# RedBoard-Artemis-Nano.net
KiCad netlist of a schematic drawn in EAGLE
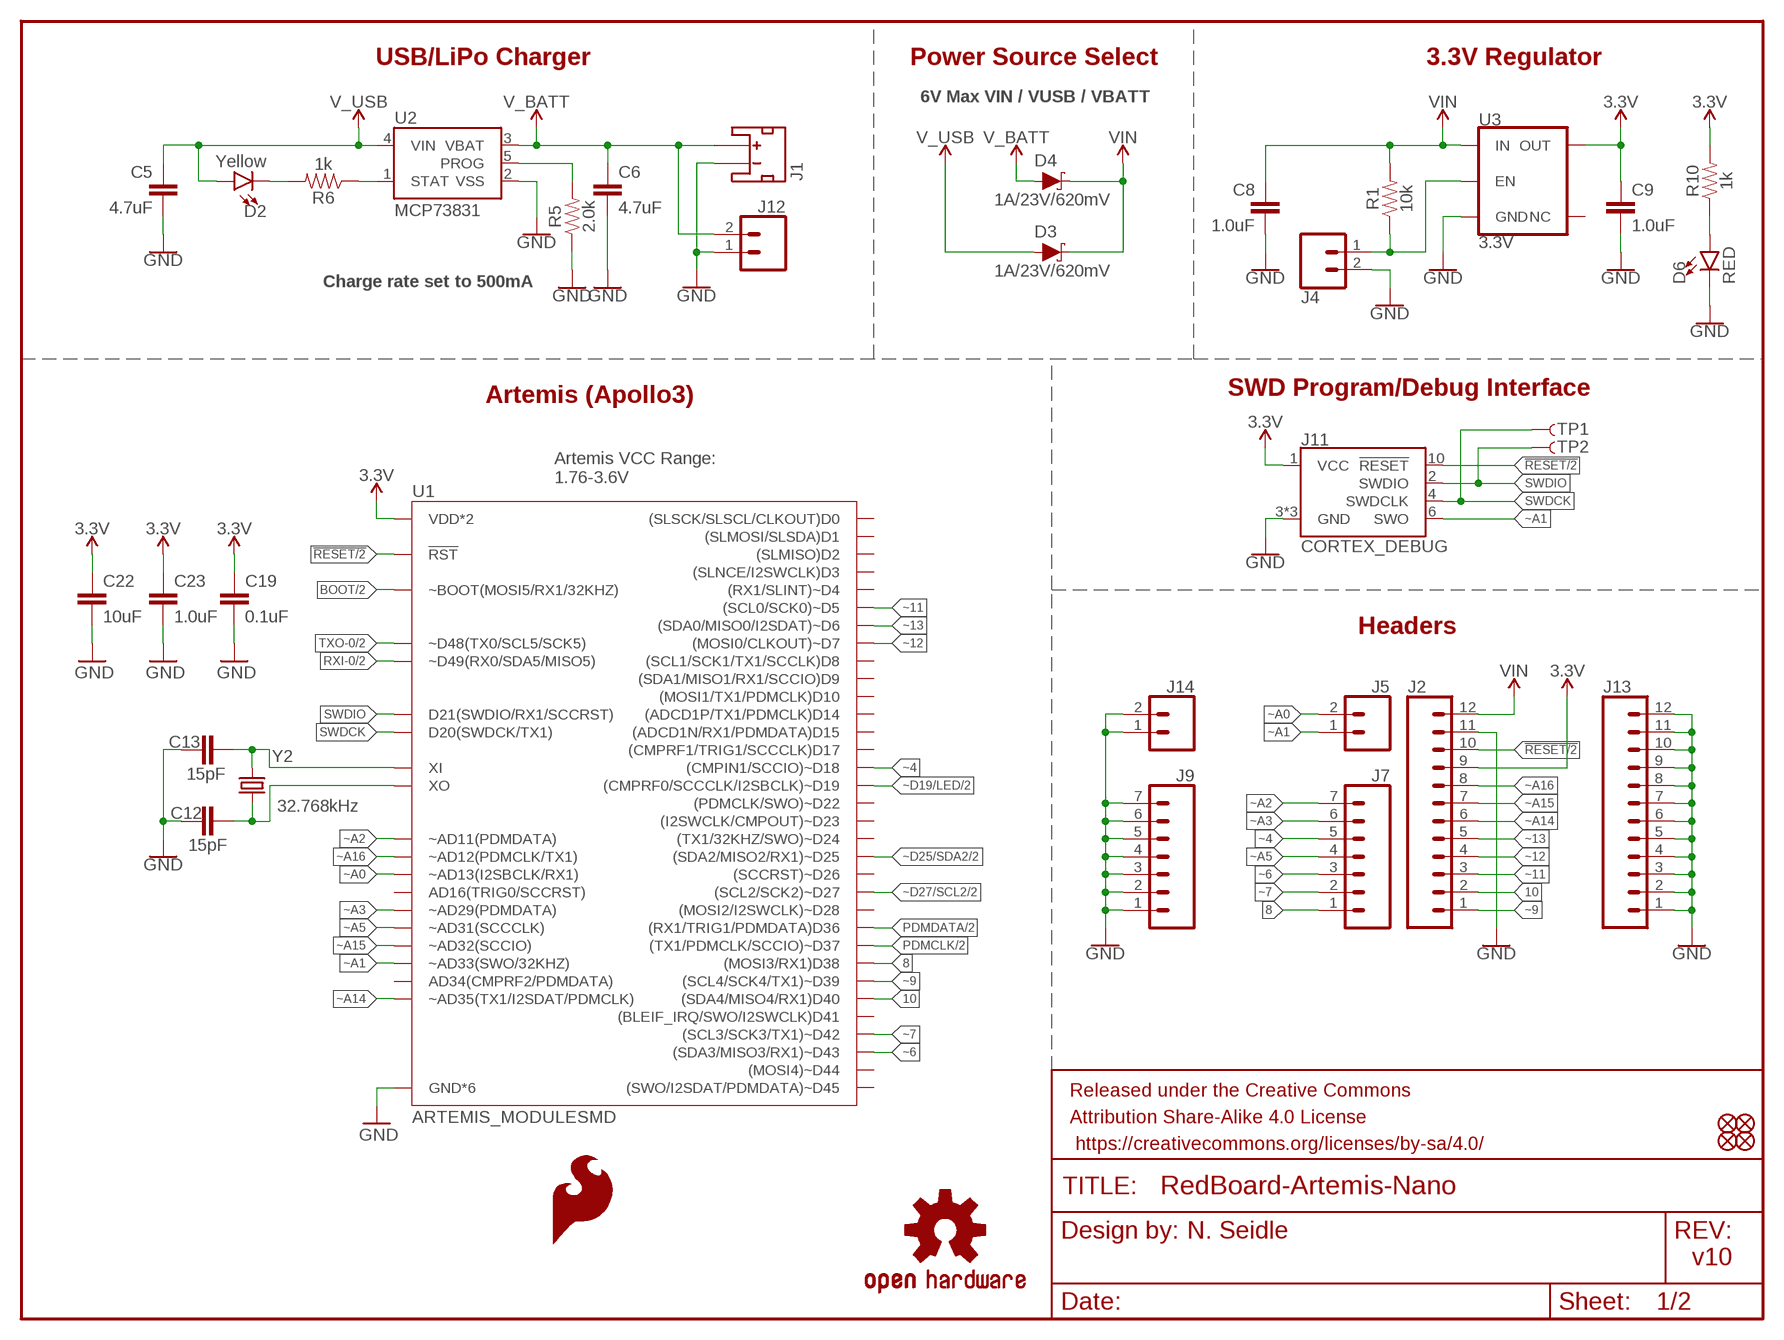
[diagram p0: schematic, sheet 1]
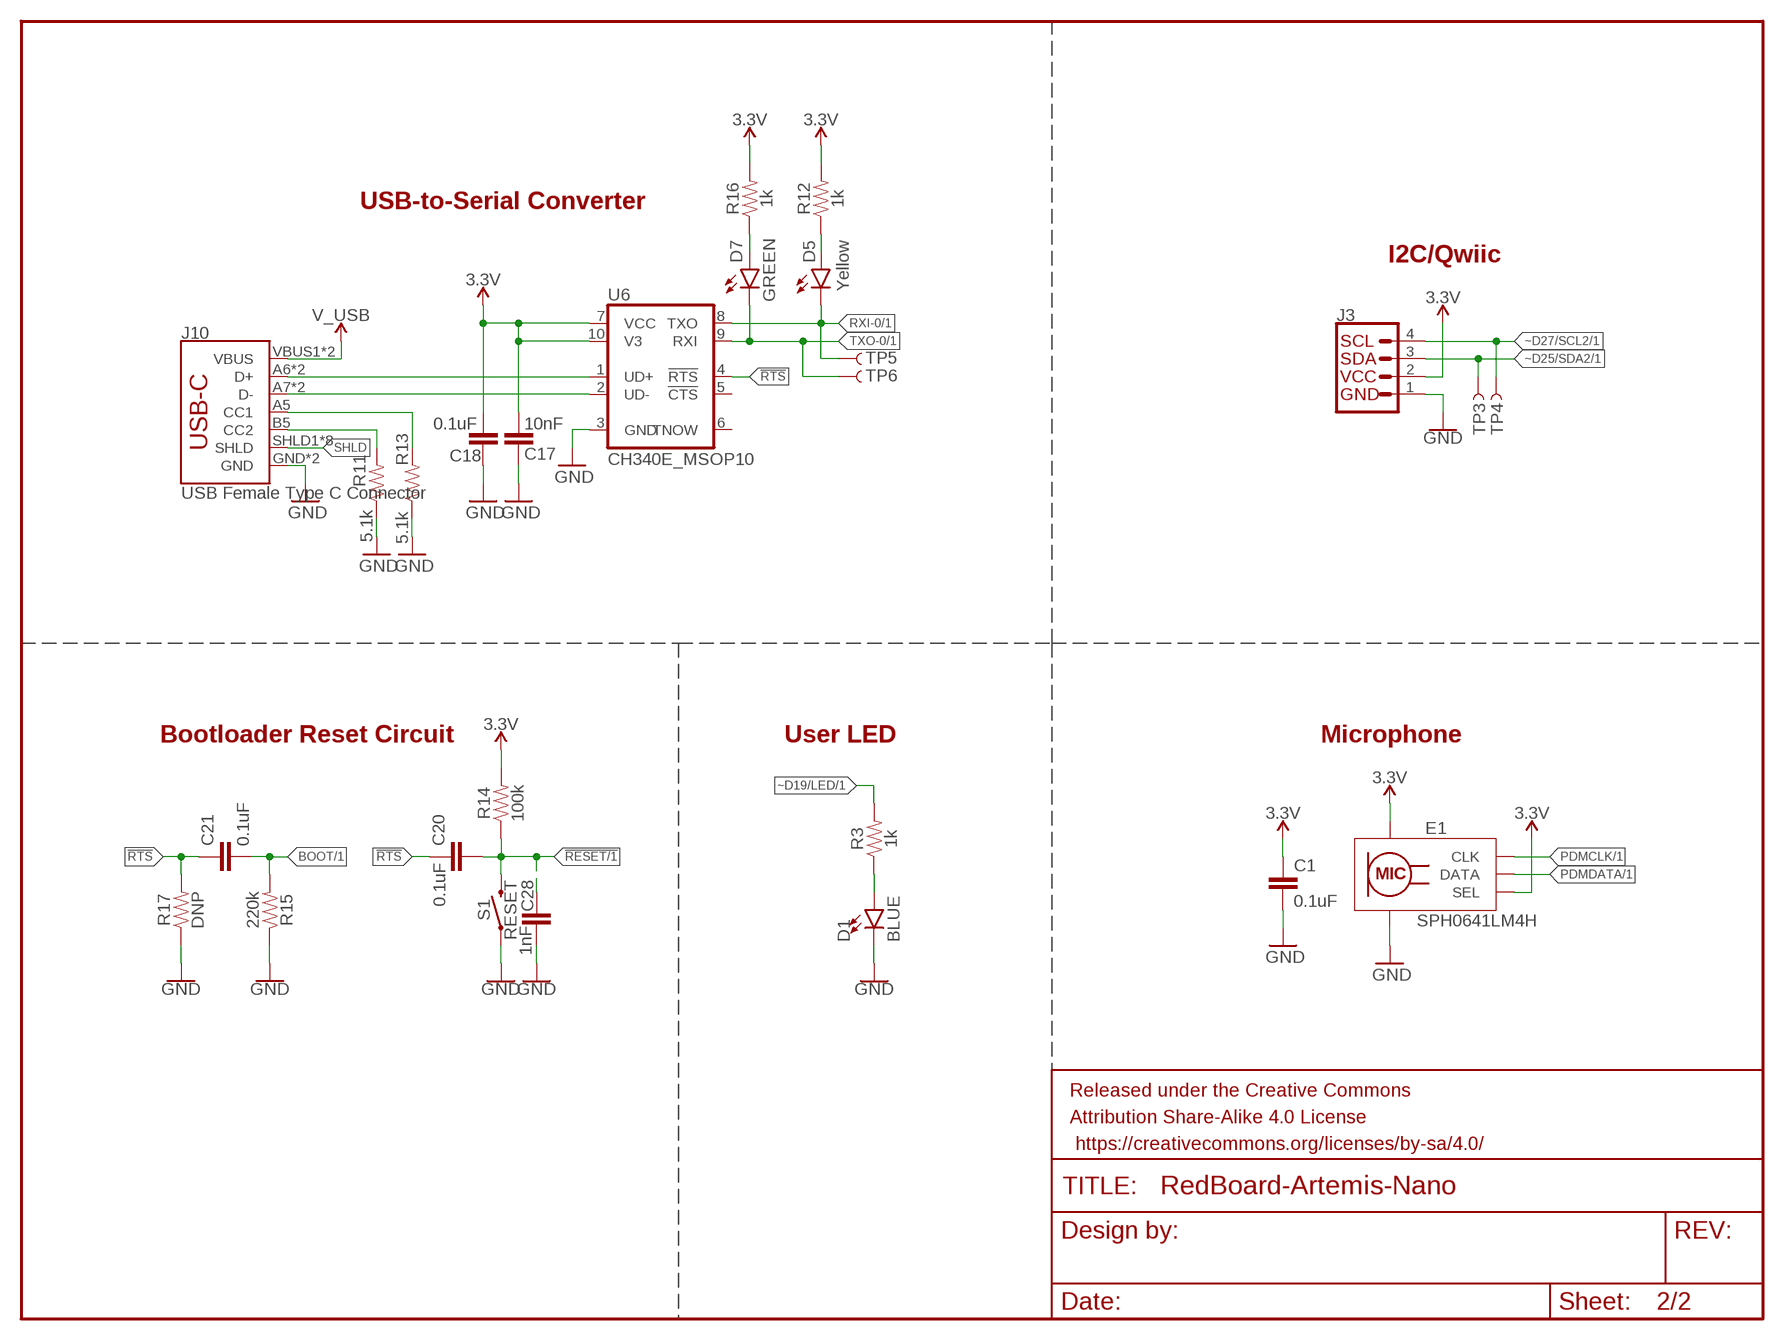
[diagram p1: schematic, sheet 2]

(export (version "E")
  (design (tool "Eeschema 10.0.6"))
  (components
    (comp (ref "C5")
      (value "4.7uF")
      (footprint "eagle-import:0603")
      (libsource (lib "eagle-import") (part "4.7UF-0603-6.3V-(10%)"))
    )
    (comp (ref "C6")
      (value "4.7uF")
      (footprint "eagle-import:0603")
      (libsource (lib "eagle-import") (part "4.7UF-0603-6.3V-(10%)"))
    )
    (comp (ref "C8")
      (value "1.0uF")
      (footprint "eagle-import:0402-TIGHT")
      (libsource (lib "eagle-import") (part "1.0UF-0402T-16V-10%"))
    )
    (comp (ref "C9")
      (value "1.0uF")
      (footprint "eagle-import:0402-TIGHT")
      (libsource (lib "eagle-import") (part "1.0UF-0402T-16V-10%"))
    )
    (comp (ref "C12")
      (value "15pF")
      (footprint "eagle-import:0603")
      (libsource (lib "eagle-import") (part "15PF-0603-50V-5%"))
    )
    (comp (ref "C13")
      (value "15pF")
      (footprint "eagle-import:0603")
      (libsource (lib "eagle-import") (part "15PF-0603-50V-5%"))
    )
    (comp (ref "C19")
      (value "0.1uF")
      (footprint "eagle-import:0402-TIGHT")
      (libsource (lib "eagle-import") (part "0.1UF-0402T-16V-10%"))
    )
    (comp (ref "C22")
      (value "10uF")
      (footprint "eagle-import:0603")
      (libsource (lib "eagle-import") (part "10UF-0603-6.3V-20%"))
    )
    (comp (ref "C23")
      (value "1.0uF")
      (footprint "eagle-import:0402-TIGHT")
      (libsource (lib "eagle-import") (part "1.0UF-0402T-16V-10%"))
    )
    (comp (ref "D2")
      (value "Yellow")
      (footprint "eagle-import:LED-0603")
      (libsource (lib "eagle-import") (part "LED-YELLOW0603"))
    )
    (comp (ref "D3")
      (value "1A/23V/620mV")
      (footprint "eagle-import:SOD-323")
      (libsource (lib "eagle-import") (part "DIODE-SCHOTTKY-BAT20J"))
    )
    (comp (ref "D4")
      (value "1A/23V/620mV")
      (footprint "eagle-import:SOD-323")
      (libsource (lib "eagle-import") (part "DIODE-SCHOTTKY-BAT20J"))
    )
    (comp (ref "D6")
      (value "RED")
      (footprint "eagle-import:LED-0603")
      (libsource (lib "eagle-import") (part "LED-RED0603"))
    )
    (comp (ref "FD1")
      (value "FIDUCIALUFIDUCIAL")
      (footprint "eagle-import:FIDUCIAL-MICRO")
      (libsource (lib "eagle-import") (part "FIDUCIALUFIDUCIAL"))
    )
    (comp (ref "FD2")
      (value "FIDUCIALUFIDUCIAL")
      (footprint "eagle-import:FIDUCIAL-MICRO")
      (libsource (lib "eagle-import") (part "FIDUCIALUFIDUCIAL"))
    )
    (comp (ref "FD3")
      (value "FIDUCIALUFIDUCIAL")
      (footprint "eagle-import:FIDUCIAL-MICRO")
      (libsource (lib "eagle-import") (part "FIDUCIALUFIDUCIAL"))
    )
    (comp (ref "FD4")
      (value "FIDUCIALUFIDUCIAL")
      (footprint "eagle-import:FIDUCIAL-MICRO")
      (libsource (lib "eagle-import") (part "FIDUCIALUFIDUCIAL"))
    )
    (comp (ref "FRAME1")
      (value "FRAME-LETTER")
      (footprint "eagle-import:CREATIVE_COMMONS")
      (libsource (lib "eagle-import") (part "FRAME-LETTER"))
    )
    (comp (ref "J1")
      (value "JST_2MM_MALE")
      (footprint "eagle-import:JST-2-SMD")
      (libsource (lib "eagle-import") (part "JST_2MM_MALE"))
    )
    (comp (ref "J2")
      (value "CONN_12NO_SILK")
      (footprint "eagle-import:1X12_NO_SILK")
      (libsource (lib "eagle-import") (part "CONN_12NO_SILK"))
    )
    (comp (ref "J4")
      (value "CONN_021X02_NO_SILK")
      (footprint "eagle-import:1X02_NO_SILK")
      (libsource (lib "eagle-import") (part "CONN_021X02_NO_SILK"))
    )
    (comp (ref "J5")
      (value "CONN_021X02_NO_SILK")
      (footprint "eagle-import:1X02_NO_SILK")
      (libsource (lib "eagle-import") (part "CONN_021X02_NO_SILK"))
    )
    (comp (ref "J7")
      (value "CONN_07NO_SILK")
      (footprint "eagle-import:1X07_NO_SILK")
      (libsource (lib "eagle-import") (part "CONN_07NO_SILK"))
    )
    (comp (ref "J9")
      (value "CONN_07NO_SILK")
      (footprint "eagle-import:1X07_NO_SILK")
      (libsource (lib "eagle-import") (part "CONN_07NO_SILK"))
    )
    (comp (ref "J11")
      (value "CORTEX_DEBUG")
      (footprint "eagle-import:2X5-PTH-1.27MM-NO_SILK")
      (libsource (lib "eagle-import") (part "CORTEX_JTAG_DEBUG_MINIMUM_PTH_NS"))
    )
    (comp (ref "J12")
      (value "CONN_021X02_NO_SILK")
      (footprint "eagle-import:1X02_NO_SILK")
      (libsource (lib "eagle-import") (part "CONN_021X02_NO_SILK"))
    )
    (comp (ref "J13")
      (value "CONN_12NO_SILK")
      (footprint "eagle-import:1X12_NO_SILK")
      (libsource (lib "eagle-import") (part "CONN_12NO_SILK"))
    )
    (comp (ref "J14")
      (value "CONN_021X02_NO_SILK")
      (footprint "eagle-import:1X02_NO_SILK")
      (libsource (lib "eagle-import") (part "CONN_021X02_NO_SILK"))
    )
    (comp (ref "LOGO1")
      (value "SFE_LOGO_FLAME.1_INCH")
      (footprint "eagle-import:SFE_LOGO_FLAME_.1")
      (libsource (lib "eagle-import") (part "SFE_LOGO_FLAME.1_INCH"))
    )
    (comp (ref "LOGO2")
      (value "OSHW-LOGONO_SILK")
      (footprint "eagle-import:DUMMY")
      (libsource (lib "eagle-import") (part "OSHW-LOGONO_SILK"))
    )
    (comp (ref "LOGO4")
      (value "SFE_LOGO_FLAME.1_INCH")
      (footprint "eagle-import:SFE_LOGO_FLAME_.1")
      (libsource (lib "eagle-import") (part "SFE_LOGO_FLAME.1_INCH"))
    )
    (comp (ref "R1")
      (value "10k")
      (footprint "eagle-import:0603")
      (libsource (lib "eagle-import") (part "10KOHM-0603-1/10W-1%"))
    )
    (comp (ref "R5")
      (value "2.0k")
      (footprint "eagle-import:0603")
      (libsource (lib "eagle-import") (part "2.0KOHM-0603-1/10W-5%"))
    )
    (comp (ref "R6")
      (value "1k")
      (footprint "eagle-import:0603")
      (libsource (lib "eagle-import") (part "1KOHM-0603-1/10W-1%"))
    )
    (comp (ref "R10")
      (value "1k")
      (footprint "eagle-import:0603")
      (libsource (lib "eagle-import") (part "1KOHM-0603-1/10W-1%"))
    )
    (comp (ref "TP1")
      (value "TEST-POINT3X5")
      (footprint "eagle-import:PAD.03X.05")
      (libsource (lib "eagle-import") (part "TEST-POINT3X5"))
    )
    (comp (ref "TP2")
      (value "TEST-POINT3X5")
      (footprint "eagle-import:PAD.03X.05")
      (libsource (lib "eagle-import") (part "TEST-POINT3X5"))
    )
    (comp (ref "U1")
      (value "ARTEMIS_MODULESMD")
      (footprint "eagle-import:ARTEMIS_FP")
      (libsource (lib "eagle-import") (part "ARTEMIS_MODULESMD"))
    )
    (comp (ref "U2")
      (value "MCP73831")
      (footprint "eagle-import:SOT23-5")
      (libsource (lib "eagle-import") (part "MCP73831"))
    )
    (comp (ref "U3")
      (value "3.3V")
      (footprint "eagle-import:SOT23-5")
      (libsource (lib "eagle-import") (part "V_REG_AP2112K-3.3V"))
    )
    (comp (ref "Y2")
      (value "32.768kHz")
      (footprint "eagle-import:CRYSTAL-SMD-3.2X1.5MM")
      (libsource (lib "eagle-import") (part "CRYSTAL-32.768KHZSMD-3.2X1.5"))
    )
    (comp (ref "C1")
      (value "0.1uF")
      (footprint "eagle-import:0402-TIGHT")
      (libsource (lib "eagle-import") (part "0.1UF-0402T-16V-10%"))
    )
    (comp (ref "C17")
      (value "10nF")
      (footprint "eagle-import:0603")
      (libsource (lib "eagle-import") (part "10NF-0603-50V-10%"))
    )
    (comp (ref "C18")
      (value "0.1uF")
      (footprint "eagle-import:0603")
      (libsource (lib "eagle-import") (part "0.1UF-0603-25V-(+80/-20%)"))
    )
    (comp (ref "C20")
      (value "0.1uF")
      (footprint "eagle-import:0603")
      (libsource (lib "eagle-import") (part "0.1UF-0603-25V-5%"))
    )
    (comp (ref "C21")
      (value "0.1uF")
      (footprint "eagle-import:0603")
      (libsource (lib "eagle-import") (part "0.1UF-0603-25V-5%"))
    )
    (comp (ref "C28")
      (value "1nF")
      (footprint "eagle-import:0603")
      (libsource (lib "eagle-import") (part "1.0NF/1000PF-0603-50V-10%"))
    )
    (comp (ref "D1")
      (value "BLUE")
      (footprint "eagle-import:LED-0603")
      (libsource (lib "eagle-import") (part "LED-BLUE0603"))
    )
    (comp (ref "D5")
      (value "Yellow")
      (footprint "eagle-import:LED-0603")
      (libsource (lib "eagle-import") (part "LED-YELLOW0603"))
    )
    (comp (ref "D7")
      (value "GREEN")
      (footprint "eagle-import:LED-0603")
      (libsource (lib "eagle-import") (part "LED-GREEN0603"))
    )
    (comp (ref "E1")
      (value "SPH0641LM4H")
      (footprint "eagle-import:SPH0641LM4H-1_MICROPHONE")
      (libsource (lib "eagle-import") (part "SPH0641LM4H-1_MICROPHONE"))
    )
    (comp (ref "FRAME2")
      (value "FRAME-LETTERNO_PACKAGE")
      (footprint "eagle-import:DUMMY")
      (fields (field (name "DESIGNER") "Nobody"))
      (libsource (lib "eagle-import") (part "FRAME-LETTERNO_PACKAGE"))
    )
    (comp (ref "J3")
      (value "QWIIC_CONNECTORJS-1MM")
      (footprint "eagle-import:JST04_1MM_RA")
      (libsource (lib "eagle-import") (part "QWIIC_CONNECTORJS-1MM"))
    )
    (comp (ref "J10")
      (value "USB Female Type C Connector")
      (footprint "eagle-import:USB-C-16P-4LAYER-ISOLATED")
      (libsource (lib "eagle-import") (part "USB_C4-LAYER-ISOLATED"))
    )
    (comp (ref "R3")
      (value "1k")
      (footprint "eagle-import:0603")
      (libsource (lib "eagle-import") (part "1KOHM-0603-1/10W-1%"))
    )
    (comp (ref "R11")
      (value "5.1k")
      (footprint "eagle-import:0603")
      (libsource (lib "eagle-import") (part "5.1KOHM5.1KOHM-0603-1/10W-1%"))
    )
    (comp (ref "R12")
      (value "1k")
      (footprint "eagle-import:0603")
      (libsource (lib "eagle-import") (part "1KOHM-0603-1/10W-1%"))
    )
    (comp (ref "R13")
      (value "5.1k")
      (footprint "eagle-import:0603")
      (libsource (lib "eagle-import") (part "5.1KOHM5.1KOHM-0603-1/10W-1%"))
    )
    (comp (ref "R14")
      (value "100k")
      (footprint "eagle-import:0603")
      (libsource (lib "eagle-import") (part "100KOHM-0603-1/10W-1%"))
    )
    (comp (ref "R15")
      (value "220k")
      (footprint "eagle-import:0603")
      (libsource (lib "eagle-import") (part "220KOHM-0603-1/10W-1%"))
    )
    (comp (ref "R16")
      (value "1k")
      (footprint "eagle-import:0603")
      (libsource (lib "eagle-import") (part "1KOHM-0603-1/10W-1%"))
    )
    (comp (ref "R17")
      (value "DNP")
      (footprint "eagle-import:0603")
      (libsource (lib "eagle-import") (part "RESISTOR0603"))
    )
    (comp (ref "S1")
      (value "RESET")
      (footprint "eagle-import:TACTILE_SWITCH_SMD_4.6X2.8MM")
      (libsource (lib "eagle-import") (part "MOMENTARY-SWITCH-SPST-SMD-4.6X2.8MM"))
    )
    (comp (ref "TP3")
      (value "TEST-POINT3X5")
      (footprint "eagle-import:PAD.03X.05")
      (libsource (lib "eagle-import") (part "TEST-POINT3X5"))
    )
    (comp (ref "TP4")
      (value "TEST-POINT3X5")
      (footprint "eagle-import:PAD.03X.05")
      (libsource (lib "eagle-import") (part "TEST-POINT3X5"))
    )
    (comp (ref "TP5")
      (value "TEST-POINT3X5")
      (footprint "eagle-import:PAD.03X.05")
      (libsource (lib "eagle-import") (part "TEST-POINT3X5"))
    )
    (comp (ref "TP6")
      (value "TEST-POINT3X5")
      (footprint "eagle-import:PAD.03X.05")
      (libsource (lib "eagle-import") (part "TEST-POINT3X5"))
    )
    (comp (ref "U6")
      (value "CH340E_MSOP10")
      (footprint "eagle-import:MSOP10")
      (libsource (lib "eagle-import") (part "CH340E_MSOP10"))
    )
  )
  (nets
    (net (code "1") (name "3.3V") (class "Default")
      (node (ref "C1") (pin "1") (pinfunction "1_1") (pintype "passive"))
      (node (ref "C17") (pin "1") (pinfunction "1_1") (pintype "passive"))
      (node (ref "C18") (pin "1") (pinfunction "1_1") (pintype "passive"))
      (node (ref "C19") (pin "2") (pinfunction "2_2") (pintype "passive"))
      (node (ref "C22") (pin "1") (pinfunction "1_1") (pintype "passive"))
      (node (ref "C23") (pin "1") (pinfunction "1_1") (pintype "passive"))
      (node (ref "C9") (pin "1") (pinfunction "1_1") (pintype "passive"))
      (node (ref "E1") (pin "2") (pinfunction "SEL_2") (pintype "input"))
      (node (ref "E1") (pin "5") (pinfunction "VDD_5") (pintype "power_in"))
      (node (ref "J11") (pin "1") (pinfunction "VCC_1") (pintype "bidirectional"))
      (node (ref "J2") (pin "9") (pinfunction "9_9") (pintype "passive"))
      (node (ref "J3") (pin "2") (pinfunction "2_2") (pintype "power_in"))
      (node (ref "R10") (pin "2") (pinfunction "2_2") (pintype "passive"))
      (node (ref "R12") (pin "2") (pinfunction "2_2") (pintype "passive"))
      (node (ref "R14") (pin "2") (pinfunction "2_2") (pintype "passive"))
      (node (ref "R16") (pin "2") (pinfunction "2_2") (pintype "passive"))
      (node (ref "U1") (pin "VDD@36") (pinfunction "VDD*2_VDD@36") (pintype "bidirectional"))
      (node (ref "U1") (pin "VDD@37") (pinfunction "VDD*2_VDD@37") (pintype "bidirectional"))
      (node (ref "U3") (pin "5") (pinfunction "OUT_5") (pintype "passive"))
      (node (ref "U6") (pin "10") (pinfunction "V3_10") (pintype "bidirectional"))
      (node (ref "U6") (pin "7") (pinfunction "VCC_7") (pintype "bidirectional"))
    )
    (net (code "2") (name "8") (class "Default")
      (node (ref "J7") (pin "1") (pinfunction "1_1") (pintype "passive"))
      (node (ref "U1") (pin "D38") (pinfunction "(MOSI3/RX1)D38_D38") (pintype "bidirectional"))
    )
    (net (code "3") (name "10") (class "Default")
      (node (ref "J2") (pin "2") (pinfunction "2_2") (pintype "passive"))
      (node (ref "U1") (pin "D40") (pinfunction "(SDA4/MISO4/RX1)D40_D40") (pintype "bidirectional"))
    )
    (net (code "4") (name "BOOT") (class "Default")
      (node (ref "C21") (pin "2") (pinfunction "2_2") (pintype "passive"))
      (node (ref "R15") (pin "2") (pinfunction "2_2") (pintype "passive"))
      (node (ref "U1") (pin "BOOT") (pinfunction "~{BOOT(MOSI5/RX1/32KHZ})_BOOT") (pintype "bidirectional"))
    )
    (net (code "5") (name "GND") (class "Default")
      (node (ref "C1") (pin "2") (pinfunction "2_2") (pintype "passive"))
      (node (ref "C12") (pin "1") (pinfunction "1_1") (pintype "passive"))
      (node (ref "C13") (pin "1") (pinfunction "1_1") (pintype "passive"))
      (node (ref "C17") (pin "2") (pinfunction "2_2") (pintype "passive"))
      (node (ref "C18") (pin "2") (pinfunction "2_2") (pintype "passive"))
      (node (ref "C19") (pin "1") (pinfunction "1_1") (pintype "passive"))
      (node (ref "C22") (pin "2") (pinfunction "2_2") (pintype "passive"))
      (node (ref "C23") (pin "2") (pinfunction "2_2") (pintype "passive"))
      (node (ref "C28") (pin "2") (pinfunction "2_2") (pintype "passive"))
      (node (ref "C5") (pin "2") (pinfunction "2_2") (pintype "passive"))
      (node (ref "C6") (pin "2") (pinfunction "2_2") (pintype "passive"))
      (node (ref "C8") (pin "2") (pinfunction "2_2") (pintype "passive"))
      (node (ref "C9") (pin "2") (pinfunction "2_2") (pintype "passive"))
      (node (ref "D1") (pin "C") (pinfunction "C_C") (pintype "passive"))
      (node (ref "D6") (pin "C") (pinfunction "C_C") (pintype "passive"))
      (node (ref "E1") (pin "3") (pinfunction "GND_3") (pintype "power_in"))
      (node (ref "E1") (pin "6") (pinfunction "GND_6") (pintype "power_in"))
      (node (ref "E1") (pin "7") (pinfunction "GND_7") (pintype "power_in"))
      (node (ref "E1") (pin "8") (pinfunction "GND_8") (pintype "power_in"))
      (node (ref "J1") (pin "1") (pinfunction "-_1") (pintype "bidirectional"))
      (node (ref "J10") (pin "GND") (pinfunction "GND_GND") (pintype "bidirectional"))
      (node (ref "J10") (pin "GND2") (pinfunction "GND_GND2") (pintype "bidirectional"))
      (node (ref "J11") (pin "3") (pinfunction "GND_3") (pintype "bidirectional"))
      (node (ref "J11") (pin "5") (pinfunction "GND_5") (pintype "bidirectional"))
      (node (ref "J11") (pin "9") (pinfunction "GND_9") (pintype "bidirectional"))
      (node (ref "J12") (pin "1") (pinfunction "1_1") (pintype "passive"))
      (node (ref "J13") (pin "1") (pinfunction "1_1") (pintype "passive"))
      (node (ref "J13") (pin "10") (pinfunction "10_10") (pintype "passive"))
      (node (ref "J13") (pin "11") (pinfunction "11_11") (pintype "passive"))
      (node (ref "J13") (pin "12") (pinfunction "12_12") (pintype "passive"))
      (node (ref "J13") (pin "2") (pinfunction "2_2") (pintype "passive"))
      (node (ref "J13") (pin "3") (pinfunction "3_3") (pintype "passive"))
      (node (ref "J13") (pin "4") (pinfunction "4_4") (pintype "passive"))
      (node (ref "J13") (pin "5") (pinfunction "5_5") (pintype "passive"))
      (node (ref "J13") (pin "6") (pinfunction "6_6") (pintype "passive"))
      (node (ref "J13") (pin "7") (pinfunction "7_7") (pintype "passive"))
      (node (ref "J13") (pin "8") (pinfunction "8_8") (pintype "passive"))
      (node (ref "J13") (pin "9") (pinfunction "9_9") (pintype "passive"))
      (node (ref "J14") (pin "1") (pinfunction "1_1") (pintype "passive"))
      (node (ref "J14") (pin "2") (pinfunction "2_2") (pintype "passive"))
      (node (ref "J2") (pin "11") (pinfunction "11_11") (pintype "passive"))
      (node (ref "J3") (pin "1") (pinfunction "1_1") (pintype "power_in"))
      (node (ref "J4") (pin "2") (pinfunction "2_2") (pintype "passive"))
      (node (ref "J9") (pin "1") (pinfunction "1_1") (pintype "passive"))
      (node (ref "J9") (pin "2") (pinfunction "2_2") (pintype "passive"))
      (node (ref "J9") (pin "3") (pinfunction "3_3") (pintype "passive"))
      (node (ref "J9") (pin "4") (pinfunction "4_4") (pintype "passive"))
      (node (ref "J9") (pin "5") (pinfunction "5_5") (pintype "passive"))
      (node (ref "J9") (pin "6") (pinfunction "6_6") (pintype "passive"))
      (node (ref "J9") (pin "7") (pinfunction "7_7") (pintype "passive"))
      (node (ref "R11") (pin "1") (pinfunction "1_1") (pintype "passive"))
      (node (ref "R13") (pin "1") (pinfunction "1_1") (pintype "passive"))
      (node (ref "R15") (pin "1") (pinfunction "1_1") (pintype "passive"))
      (node (ref "R17") (pin "1") (pinfunction "1_1") (pintype "passive"))
      (node (ref "R5") (pin "1") (pinfunction "1_1") (pintype "passive"))
      (node (ref "S1") (pin "1") (pinfunction "1_1") (pintype "passive"))
      (node (ref "S1") (pin "2") (pinfunction "1_2") (pintype "passive"))
      (node (ref "U1") (pin "GND@1") (pinfunction "GND*6_GND@1") (pintype "bidirectional"))
      (node (ref "U1") (pin "GND@22") (pinfunction "GND*6_GND@22") (pintype "bidirectional"))
      (node (ref "U1") (pin "GND@38") (pinfunction "GND*6_GND@38") (pintype "bidirectional"))
      (node (ref "U1") (pin "GND@39") (pinfunction "GND*6_GND@39") (pintype "bidirectional"))
      (node (ref "U1") (pin "GND@47") (pinfunction "GND*6_GND@47") (pintype "bidirectional"))
      (node (ref "U1") (pin "GND@59") (pinfunction "GND*6_GND@59") (pintype "bidirectional"))
      (node (ref "U2") (pin "2") (pinfunction "VSS_2") (pintype "power_in"))
      (node (ref "U3") (pin "2") (pinfunction "GND_2") (pintype "input"))
      (node (ref "U6") (pin "3") (pinfunction "GND_3") (pintype "bidirectional"))
    )
    (net (code "6") (name "Net-(D1-PadA)") (class "Default")
      (node (ref "D1") (pin "A") (pinfunction "A_A") (pintype "passive"))
      (node (ref "R3") (pin "1") (pinfunction "1_1") (pintype "passive"))
    )
    (net (code "7") (name "Net-(D2-PadC)") (class "Default")
      (node (ref "D2") (pin "C") (pinfunction "C_C") (pintype "passive"))
      (node (ref "R6") (pin "2") (pinfunction "2_2") (pintype "passive"))
    )
    (net (code "8") (name "Net-(D5-PadA)") (class "Default")
      (node (ref "D5") (pin "A") (pinfunction "A_A") (pintype "passive"))
      (node (ref "R12") (pin "1") (pinfunction "1_1") (pintype "passive"))
    )
    (net (code "9") (name "Net-(D6-PadA)") (class "Default")
      (node (ref "D6") (pin "A") (pinfunction "A_A") (pintype "passive"))
      (node (ref "R10") (pin "1") (pinfunction "1_1") (pintype "passive"))
    )
    (net (code "10") (name "Net-(D7-PadA)") (class "Default")
      (node (ref "D7") (pin "A") (pinfunction "A_A") (pintype "passive"))
      (node (ref "R16") (pin "1") (pinfunction "1_1") (pintype "passive"))
    )
    (net (code "11") (name "Net-(J10-CC1)") (class "Default")
      (node (ref "J10") (pin "A5") (pinfunction "CC1_A5") (pintype "bidirectional"))
      (node (ref "R13") (pin "2") (pinfunction "2_2") (pintype "passive"))
    )
    (net (code "12") (name "Net-(J10-CC2)") (class "Default")
      (node (ref "J10") (pin "B5") (pinfunction "CC2_B5") (pintype "bidirectional"))
      (node (ref "R11") (pin "2") (pinfunction "2_2") (pintype "passive"))
    )
    (net (code "13") (name "Net-(U2-PROG)") (class "Default")
      (node (ref "R5") (pin "2") (pinfunction "2_2") (pintype "passive"))
      (node (ref "U2") (pin "5") (pinfunction "PROG_5") (pintype "input"))
    )
    (net (code "14") (name "Net-(U2-STAT)") (class "Default")
      (node (ref "R6") (pin "1") (pinfunction "1_1") (pintype "passive"))
      (node (ref "U2") (pin "1") (pinfunction "STAT_1") (pintype "output"))
    )
    (net (code "15") (name "Net-(U3-EN)") (class "Default")
      (node (ref "J4") (pin "1") (pinfunction "1_1") (pintype "passive"))
      (node (ref "R1") (pin "1") (pinfunction "1_1") (pintype "passive"))
      (node (ref "U3") (pin "3") (pinfunction "EN_3") (pintype "input"))
    )
    (net (code "16") (name "Net-(U6-UD+)") (class "Default")
      (node (ref "J10") (pin "A6") (pinfunction "D+_A6") (pintype "bidirectional"))
      (node (ref "J10") (pin "B6") (pinfunction "D+_B6") (pintype "bidirectional"))
      (node (ref "U6") (pin "1") (pinfunction "UD+_1") (pintype "bidirectional"))
    )
    (net (code "17") (name "Net-(U6-UD-)") (class "Default")
      (node (ref "J10") (pin "A7") (pinfunction "D-_A7") (pintype "bidirectional"))
      (node (ref "J10") (pin "B7") (pinfunction "D-_B7") (pintype "bidirectional"))
      (node (ref "U6") (pin "2") (pinfunction "UD-_2") (pintype "bidirectional"))
    )
    (net (code "18") (name "Net-(Y2-1)") (class "Default")
      (node (ref "C13") (pin "2") (pinfunction "2_2") (pintype "passive"))
      (node (ref "U1") (pin "XI") (pinfunction "XI_XI") (pintype "bidirectional"))
      (node (ref "Y2") (pin "P$1") (pinfunction "1_P$1") (pintype "passive"))
    )
    (net (code "19") (name "Net-(Y2-2)") (class "Default")
      (node (ref "C12") (pin "2") (pinfunction "2_2") (pintype "passive"))
      (node (ref "U1") (pin "XO") (pinfunction "XO_XO") (pintype "bidirectional"))
      (node (ref "Y2") (pin "P$2") (pinfunction "2_P$2") (pintype "passive"))
    )
    (net (code "20") (name "PDMCLK") (class "Default")
      (node (ref "E1") (pin "4") (pinfunction "CLK_4") (pintype "input"))
      (node (ref "U1") (pin "~D37") (pinfunction "(TX1/PDMCLK/SCCIO)~{D37}_~D37") (pintype "bidirectional"))
    )
    (net (code "21") (name "PDMDATA") (class "Default")
      (node (ref "E1") (pin "1") (pinfunction "DATA_1") (pintype "output"))
      (node (ref "U1") (pin "D36") (pinfunction "(RX1/TRIG1/PDMDATA)D36_D36") (pintype "bidirectional"))
    )
    (net (code "22") (name "RXI-0") (class "Default")
      (node (ref "D5") (pin "C") (pinfunction "C_C") (pintype "passive"))
      (node (ref "TP5") (pin "P$1") (pinfunction "1_P$1") (pintype "bidirectional"))
      (node (ref "U1") (pin "RXI-0") (pinfunction "~{D49(RX0/SDA5/MISO5})_RXI-0") (pintype "bidirectional"))
      (node (ref "U6") (pin "8") (pinfunction "TXO_8") (pintype "bidirectional"))
    )
    (net (code "23") (name "SHLD") (class "Default")
      (node (ref "J10") (pin "SHLD1") (pinfunction "SHLD_SHLD1") (pintype "bidirectional"))
      (node (ref "J10") (pin "SHLD2") (pinfunction "SHLD_SHLD2") (pintype "bidirectional"))
      (node (ref "J10") (pin "SHLD3") (pinfunction "SHLD_SHLD3") (pintype "bidirectional"))
      (node (ref "J10") (pin "SHLD4") (pinfunction "SHLD_SHLD4") (pintype "bidirectional"))
      (node (ref "J10") (pin "SHLD5") (pinfunction "SHLD_SHLD5") (pintype "bidirectional"))
      (node (ref "J10") (pin "SHLD6") (pinfunction "SHLD_SHLD6") (pintype "bidirectional"))
      (node (ref "J10") (pin "SHLD7") (pinfunction "SHLD_SHLD7") (pintype "bidirectional"))
      (node (ref "J10") (pin "SHLD8") (pinfunction "SHLD_SHLD8") (pintype "bidirectional"))
    )
    (net (code "24") (name "SWDCK") (class "Default")
      (node (ref "J11") (pin "4") (pinfunction "SWDCLK_4") (pintype "bidirectional"))
      (node (ref "TP1") (pin "P$1") (pinfunction "1_P$1") (pintype "bidirectional"))
      (node (ref "U1") (pin "SWDCK") (pinfunction "D20(SWDCK/TX1)_SWDCK") (pintype "bidirectional"))
    )
    (net (code "25") (name "SWDIO") (class "Default")
      (node (ref "J11") (pin "2") (pinfunction "SWDIO_2") (pintype "bidirectional"))
      (node (ref "TP2") (pin "P$1") (pinfunction "1_P$1") (pintype "bidirectional"))
      (node (ref "U1") (pin "SWDIO") (pinfunction "D21(SWDIO/RX1/SCCRST)_SWDIO") (pintype "bidirectional"))
    )
    (net (code "26") (name "TXO-0") (class "Default")
      (node (ref "D7") (pin "C") (pinfunction "C_C") (pintype "passive"))
      (node (ref "TP6") (pin "P$1") (pinfunction "1_P$1") (pintype "bidirectional"))
      (node (ref "U1") (pin "TXO-0") (pinfunction "~{D48(TX0/SCL5/SCK5})_TXO-0") (pintype "bidirectional"))
      (node (ref "U6") (pin "9") (pinfunction "RXI_9") (pintype "bidirectional"))
    )
    (net (code "27") (name "VIN") (class "Default")
      (node (ref "C8") (pin "1") (pinfunction "1_1") (pintype "passive"))
      (node (ref "D3") (pin "C") (pinfunction "C_C") (pintype "passive"))
      (node (ref "D4") (pin "C") (pinfunction "C_C") (pintype "passive"))
      (node (ref "J2") (pin "12") (pinfunction "12_12") (pintype "passive"))
      (node (ref "R1") (pin "2") (pinfunction "2_2") (pintype "passive"))
      (node (ref "U3") (pin "1") (pinfunction "IN_1") (pintype "input"))
    )
    (net (code "28") (name "V_BATT") (class "Default")
      (node (ref "C6") (pin "1") (pinfunction "1_1") (pintype "passive"))
      (node (ref "D4") (pin "A") (pinfunction "A_A") (pintype "passive"))
      (node (ref "J1") (pin "2") (pinfunction "+_2") (pintype "bidirectional"))
      (node (ref "J12") (pin "2") (pinfunction "2_2") (pintype "passive"))
      (node (ref "U2") (pin "3") (pinfunction "VBAT_3") (pintype "power_in"))
    )
    (net (code "29") (name "V_USB") (class "Default")
      (node (ref "C5") (pin "1") (pinfunction "1_1") (pintype "passive"))
      (node (ref "D2") (pin "A") (pinfunction "A_A") (pintype "passive"))
      (node (ref "D3") (pin "A") (pinfunction "A_A") (pintype "passive"))
      (node (ref "J10") (pin "VBUS1") (pinfunction "VBUS_VBUS1") (pintype "bidirectional"))
      (node (ref "J10") (pin "VBUS2") (pinfunction "VBUS_VBUS2") (pintype "bidirectional"))
      (node (ref "U2") (pin "4") (pinfunction "VIN_4") (pintype "power_in"))
    )
    (net (code "30") (name "unconnected-(J1-PAD1-PadNC1)") (class "Default")
      (node (ref "J1") (pin "NC1") (pinfunction "PAD1_NC1") (pintype "bidirectional"))
    )
    (net (code "31") (name "unconnected-(J1-PAD2-PadNC2)") (class "Default")
      (node (ref "J1") (pin "NC2") (pinfunction "PAD2_NC2") (pintype "bidirectional"))
    )
    (net (code "32") (name "unconnected-(U1-(ADCD1N{slash}RX1{slash}PDMDATA)D15-PadD15)") (class "Default")
      (node (ref "U1") (pin "D15") (pinfunction "(ADCD1N/RX1/PDMDATA)D15_D15") (pintype "bidirectional"))
    )
    (net (code "33") (name "unconnected-(U1-(ADCD1P{slash}TX1{slash}PDMCLK)D14-PadD14)") (class "Default")
      (node (ref "U1") (pin "D14") (pinfunction "(ADCD1P/TX1/PDMCLK)D14_D14") (pintype "bidirectional"))
    )
    (net (code "34") (name "unconnected-(U1-(BLEIF_IRQ{slash}SWO{slash}I2SWCLK)D41-PadD41)") (class "Default")
      (node (ref "U1") (pin "D41") (pinfunction "(BLEIF_IRQ/SWO/I2SWCLK)D41_D41") (pintype "bidirectional"))
    )
    (net (code "35") (name "unconnected-(U1-(CMPRF1{slash}TRIG1{slash}SCCCLK)D17-PadD17)") (class "Default")
      (node (ref "U1") (pin "D17") (pinfunction "(CMPRF1/TRIG1/SCCCLK)D17_D17") (pintype "bidirectional"))
    )
    (net (code "36") (name "unconnected-(U1-(I2SWCLK{slash}CMPOUT)~{D23}-Pad~D23)") (class "Default")
      (node (ref "U1") (pin "~D23") (pinfunction "(I2SWCLK/CMPOUT)~{D23}_~D23") (pintype "bidirectional"))
    )
    (net (code "37") (name "unconnected-(U1-(MOSI1{slash}TX1{slash}PDMCLK)D10-PadD10)") (class "Default")
      (node (ref "U1") (pin "D10") (pinfunction "(MOSI1/TX1/PDMCLK)D10_D10") (pintype "bidirectional"))
    )
    (net (code "38") (name "unconnected-(U1-(MOSI2{slash}I2SWCLK)~{D28}-Pad~D28)") (class "Default")
      (node (ref "U1") (pin "~D28") (pinfunction "(MOSI2/I2SWCLK)~{D28}_~D28") (pintype "bidirectional"))
    )
    (net (code "39") (name "unconnected-(U1-(MOSI4)~{D44}-Pad~D44)") (class "Default")
      (node (ref "U1") (pin "~D44") (pinfunction "(MOSI4)~{D44}_~D44") (pintype "bidirectional"))
    )
    (net (code "40") (name "unconnected-(U1-(PDMCLK{slash}SWO)~{D22}-Pad~D22)") (class "Default")
      (node (ref "U1") (pin "~D22") (pinfunction "(PDMCLK/SWO)~{D22}_~D22") (pintype "bidirectional"))
    )
    (net (code "41") (name "unconnected-(U1-(RX1{slash}SLINT)~{D4}-Pad~D4)") (class "Default")
      (node (ref "U1") (pin "~D4") (pinfunction "(RX1/SLINT)~{D4}_~D4") (pintype "bidirectional"))
    )
    (net (code "42") (name "unconnected-(U1-(SCCRST)~{D26}-Pad~D26)") (class "Default")
      (node (ref "U1") (pin "~D26") (pinfunction "(SCCRST)~{D26}_~D26") (pintype "bidirectional"))
    )
    (net (code "43") (name "unconnected-(U1-(SCL1{slash}SCK1{slash}TX1{slash}SCCLK)D8-PadD8)") (class "Default")
      (node (ref "U1") (pin "D8") (pinfunction "(SCL1/SCK1/TX1/SCCLK)D8_D8") (pintype "bidirectional"))
    )
    (net (code "44") (name "unconnected-(U1-(SDA1{slash}MISO1{slash}RX1{slash}SCCIO)D9-PadD9)") (class "Default")
      (node (ref "U1") (pin "D9") (pinfunction "(SDA1/MISO1/RX1/SCCIO)D9_D9") (pintype "bidirectional"))
    )
    (net (code "45") (name "unconnected-(U1-(SLMISO)D2-PadD2)") (class "Default")
      (node (ref "U1") (pin "D2") (pinfunction "(SLMISO)D2_D2") (pintype "bidirectional"))
    )
    (net (code "46") (name "unconnected-(U1-(SLMOSI{slash}SLSDA)D1-PadD1)") (class "Default")
      (node (ref "U1") (pin "D1") (pinfunction "(SLMOSI/SLSDA)D1_D1") (pintype "bidirectional"))
    )
    (net (code "47") (name "unconnected-(U1-(SLNCE{slash}I2SWCLK)D3-PadD3)") (class "Default")
      (node (ref "U1") (pin "D3") (pinfunction "(SLNCE/I2SWCLK)D3_D3") (pintype "bidirectional"))
    )
    (net (code "48") (name "unconnected-(U1-(SLSCK{slash}SLSCL{slash}CLKOUT)D0-PadD0)") (class "Default")
      (node (ref "U1") (pin "D0") (pinfunction "(SLSCK/SLSCL/CLKOUT)D0_D0") (pintype "bidirectional"))
    )
    (net (code "49") (name "unconnected-(U1-(SWO{slash}I2SDAT{slash}PDMDATA)~{D45}-Pad~D45)") (class "Default")
      (node (ref "U1") (pin "~D45") (pinfunction "(SWO/I2SDAT/PDMDATA)~{D45}_~D45") (pintype "bidirectional"))
    )
    (net (code "50") (name "unconnected-(U1-(TX1{slash}32KHZ{slash}SWO)~{D24}-Pad~D24)") (class "Default")
      (node (ref "U1") (pin "~D24") (pinfunction "(TX1/32KHZ/SWO)~{D24}_~D24") (pintype "bidirectional"))
    )
    (net (code "51") (name "unconnected-(U1-AD16(TRIG0{slash}SCCRST)-PadAD16)") (class "Default")
      (node (ref "U1") (pin "AD16") (pinfunction "AD16(TRIG0/SCCRST)_AD16") (pintype "bidirectional"))
    )
    (net (code "52") (name "unconnected-(U1-AD34(CMPRF2{slash}PDMDATA)-PadAD34)") (class "Default")
      (node (ref "U1") (pin "AD34") (pinfunction "AD34(CMPRF2/PDMDATA)_AD34") (pintype "bidirectional"))
    )
    (net (code "53") (name "unconnected-(U3-NC-Pad4)") (class "Default")
      (node (ref "U3") (pin "4") (pinfunction "NC_4") (pintype "no_connect"))
    )
    (net (code "54") (name "unconnected-(U6-TNOW-Pad6)") (class "Default")
      (node (ref "U6") (pin "6") (pinfunction "TNOW_6") (pintype "bidirectional"))
    )
    (net (code "55") (name "unconnected-(U6-~{CTS}-Pad5)") (class "Default")
      (node (ref "U6") (pin "5") (pinfunction "~{CTS}_5") (pintype "bidirectional"))
    )
    (net (code "56") (name "~{4}") (class "Default")
      (node (ref "J7") (pin "5") (pinfunction "5_5") (pintype "passive"))
      (node (ref "U1") (pin "~D18") (pinfunction "(CMPIN1/SCCIO)~{D18}_~D18") (pintype "bidirectional"))
    )
    (net (code "57") (name "~{6}") (class "Default")
      (node (ref "J7") (pin "3") (pinfunction "3_3") (pintype "passive"))
      (node (ref "U1") (pin "~D43") (pinfunction "(SDA3/MISO3/RX1)~{D43}_~D43") (pintype "bidirectional"))
    )
    (net (code "58") (name "~{7}") (class "Default")
      (node (ref "J7") (pin "2") (pinfunction "2_2") (pintype "passive"))
      (node (ref "U1") (pin "~D42") (pinfunction "(SCL3/SCK3/TX1)~{D42}_~D42") (pintype "bidirectional"))
    )
    (net (code "59") (name "~{9}") (class "Default")
      (node (ref "J2") (pin "1") (pinfunction "1_1") (pintype "passive"))
      (node (ref "U1") (pin "~D39") (pinfunction "(SCL4/SCK4/TX1)~{D39}_~D39") (pintype "bidirectional"))
    )
    (net (code "60") (name "~{11}") (class "Default")
      (node (ref "J2") (pin "3") (pinfunction "3_3") (pintype "passive"))
      (node (ref "U1") (pin "~D5") (pinfunction "(SCL0/SCK0)~{D5}_~D5") (pintype "bidirectional"))
    )
    (net (code "61") (name "~{12}") (class "Default")
      (node (ref "J2") (pin "4") (pinfunction "4_4") (pintype "passive"))
      (node (ref "U1") (pin "D7") (pinfunction "(MOSI0/CLKOUT)~{D7}_D7") (pintype "bidirectional"))
    )
    (net (code "62") (name "~{13}") (class "Default")
      (node (ref "J2") (pin "5") (pinfunction "5_5") (pintype "passive"))
      (node (ref "U1") (pin "~D6") (pinfunction "(SDA0/MISO0/I2SDAT)~{D6}_~D6") (pintype "bidirectional"))
    )
    (net (code "63") (name "~{A0}") (class "Default")
      (node (ref "J5") (pin "2") (pinfunction "2_2") (pintype "passive"))
      (node (ref "U1") (pin "~AD13") (pinfunction "~{AD13(I2SBCLK/RX1})_~AD13") (pintype "bidirectional"))
    )
    (net (code "64") (name "~{A1}") (class "Default")
      (node (ref "J11") (pin "6") (pinfunction "SWO_6") (pintype "bidirectional"))
      (node (ref "J5") (pin "1") (pinfunction "1_1") (pintype "passive"))
      (node (ref "U1") (pin "~AD33/SWO") (pinfunction "~{AD33(SWO/32KHZ})_~AD33/SWO") (pintype "bidirectional"))
    )
    (net (code "65") (name "~{A2}") (class "Default")
      (node (ref "J7") (pin "7") (pinfunction "7_7") (pintype "passive"))
      (node (ref "U1") (pin "~AD11") (pinfunction "~{AD11(PDMDATA})_~AD11") (pintype "bidirectional"))
    )
    (net (code "66") (name "~{A3}") (class "Default")
      (node (ref "J7") (pin "6") (pinfunction "6_6") (pintype "passive"))
      (node (ref "U1") (pin "~AD29") (pinfunction "~{AD29(PDMDATA})_~AD29") (pintype "bidirectional"))
    )
    (net (code "67") (name "~{A5}") (class "Default")
      (node (ref "J7") (pin "4") (pinfunction "4_4") (pintype "passive"))
      (node (ref "U1") (pin "~AD31") (pinfunction "~{AD31(SCCCLK})_~AD31") (pintype "bidirectional"))
    )
    (net (code "68") (name "~{A14}") (class "Default")
      (node (ref "J2") (pin "6") (pinfunction "6_6") (pintype "passive"))
      (node (ref "U1") (pin "~AD35") (pinfunction "~{AD35(TX1/I2SDAT/PDMCLK})_~AD35") (pintype "bidirectional"))
    )
    (net (code "69") (name "~{A15}") (class "Default")
      (node (ref "J2") (pin "7") (pinfunction "7_7") (pintype "passive"))
      (node (ref "U1") (pin "~AD32") (pinfunction "~{AD32(SCCIO})_~AD32") (pintype "bidirectional"))
    )
    (net (code "70") (name "~{A16}") (class "Default")
      (node (ref "J2") (pin "8") (pinfunction "8_8") (pintype "passive"))
      (node (ref "U1") (pin "~AD12") (pinfunction "~{AD12(PDMCLK/TX1})_~AD12") (pintype "bidirectional"))
    )
    (net (code "71") (name "~{D19{slash}LED}") (class "Default")
      (node (ref "R3") (pin "2") (pinfunction "2_2") (pintype "passive"))
      (node (ref "U1") (pin "~D19") (pinfunction "(CMPRF0/SCCCLK/I2SBCLK)~{D19}_~D19") (pintype "bidirectional"))
    )
    (net (code "72") (name "~{D25{slash}SDA2}") (class "Default")
      (node (ref "J3") (pin "3") (pinfunction "3_3") (pintype "passive"))
      (node (ref "TP3") (pin "P$1") (pinfunction "1_P$1") (pintype "bidirectional"))
      (node (ref "U1") (pin "~D25") (pinfunction "(SDA2/MISO2/RX1)~{D25}_~D25") (pintype "bidirectional"))
    )
    (net (code "73") (name "~{D27{slash}SCL2}") (class "Default")
      (node (ref "J3") (pin "4") (pinfunction "4_4") (pintype "passive"))
      (node (ref "TP4") (pin "P$1") (pinfunction "1_P$1") (pintype "bidirectional"))
      (node (ref "U1") (pin "~D27") (pinfunction "(SCL2/SCK2)~{D27}_~D27") (pintype "bidirectional"))
    )
    (net (code "74") (name "~{RESET}") (class "Default")
      (node (ref "C20") (pin "2") (pinfunction "2_2") (pintype "passive"))
      (node (ref "C28") (pin "1") (pinfunction "1_1") (pintype "passive"))
      (node (ref "J11") (pin "10") (pinfunction "~{RESET}_10") (pintype "bidirectional"))
      (node (ref "J2") (pin "10") (pinfunction "10_10") (pintype "passive"))
      (node (ref "R14") (pin "1") (pinfunction "1_1") (pintype "passive"))
      (node (ref "S1") (pin "3") (pinfunction "2_3") (pintype "passive"))
      (node (ref "S1") (pin "4") (pinfunction "2_4") (pintype "passive"))
      (node (ref "U1") (pin "~RST") (pinfunction "~{RST}_~RST") (pintype "bidirectional"))
    )
    (net (code "75") (name "~{RTS}") (class "Default")
      (node (ref "C20") (pin "1") (pinfunction "1_1") (pintype "passive"))
      (node (ref "C21") (pin "1") (pinfunction "1_1") (pintype "passive"))
      (node (ref "R17") (pin "2") (pinfunction "2_2") (pintype "passive"))
      (node (ref "U6") (pin "4") (pinfunction "~{RTS}_4") (pintype "bidirectional"))
    )
  )
)
